# MelansonTech_PSU_IsolatedShuntAmp.net
KiCad netlist of a schematic drawn in Altium Designer
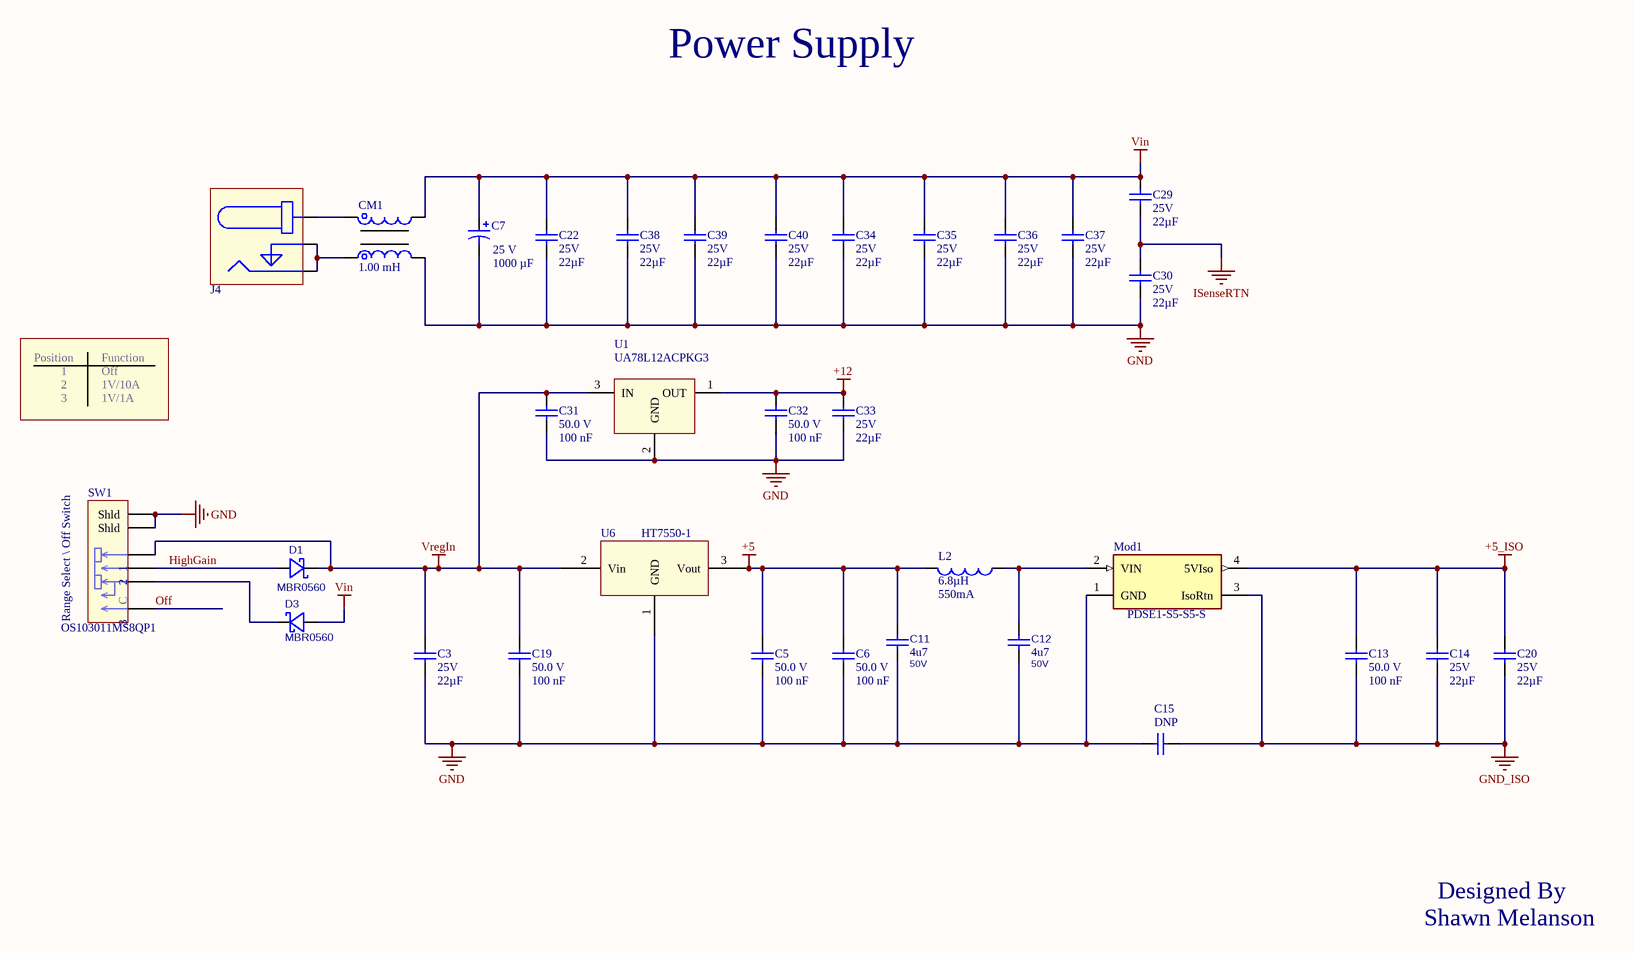
[diagram p0: MelansonTech PSU_IsolatedShuntAmp.SchDoc]

(export (version "E")
  (design (tool "Eeschema 10.0.6"))
  (components
    (comp (ref "C3")
      (value "CL21A226MAQNNNE")
      (footprint "Cap,0805")
      (description "CAP CER 22UF 25V X5R 0805")
      (fields
        (field (name "MANUFACTURER") "Samsung Electro-Mechanics")
        (field (name "TOLERANCE") "±20%")
        (field (name "VOLTAGE - RATED") "25V")
        (field (name "CAPACITANCE") "22µF")
      )
      (libsource (lib "Master Mar2024") (part "Cap,0805,22uF,25V,X5R,±20%,CL21A226MAQNNNE"))
    )
    (comp (ref "C5")
      (value "CC0805KRX7R9BB104")
      (footprint "CAP, 0805, HD")
      (description "CAP CER 0.1UF 50V X7R 0805")
      (fields
        (field (name "VOLTAGE RATING (DC)") "50.0 V")
        (field (name "CAPACITANCE") "100 nF")
        (field (name "MANUFACTURER") "YAGEO")
      )
      (libsource (lib "Master Mar2024") (part "Cap,0805,100nf,50V,5%,CC0805KRX7R9BB104"))
    )
    (comp (ref "C6")
      (value "CC0805KRX7R9BB104")
      (footprint "CAP, 0805, HD")
      (description "CAP CER 0.1UF 50V X7R 0805")
      (fields
        (field (name "VOLTAGE RATING (DC)") "50.0 V")
        (field (name "CAPACITANCE") "100 nF")
        (field (name "MANUFACTURER") "YAGEO")
      )
      (libsource (lib "Master Mar2024") (part "Cap,0805,100nf,50V,5%,CC0805KRX7R9BB104"))
    )
    (comp (ref "C7")
      (value "A750MV108M1EAAE014")
      (footprint "Cap,5mm Lead Spaceing,14mm HIGH,10MM Dia, Polymer - RA1")
      (description "1000 µF 25 V Aluminum - Polymer Capacitors Radial, Can 14mOhm 2000 Hrs @ 105°C")
      (fields
        (field (name "MANUFACTURER") "KEMET")
        (field (name "CAPACITANCE") "1000 µF")
        (field (name "TOLERANCE") "±20%")
        (field (name "VOLTAGE - RATED") "25 V")
      )
      (libsource (lib "Master Mar2024") (part "Cap,Polar,TH,1000uF,25V,Polymer,±20%,A750MV108M1EAAE014"))
    )
    (comp (ref "C11")
      (value "CL31B475KBHNNNE")
      (footprint "Cap, 1206")
      (description "Cap,SMD,MLCC,4u7,50V,X7R,10%,1206")
      (fields
        (field (name "MANUFACTURER") "Samsung")
        (field (name "TOLERANCE") "10%")
        (field (name "CAPACITANCE") "4u7")
        (field (name "VOLTAGE") "50V")
      )
      (libsource (lib "Master JULY2019") (part "Cap,1206,4.7uF,10%,50V,CL31B475KBHNNNE"))
    )
    (comp (ref "C12")
      (value "CL31B475KBHNNNE")
      (footprint "Cap, 1206")
      (description "Cap,SMD,MLCC,4u7,50V,X7R,10%,1206")
      (fields
        (field (name "MANUFACTURER") "Samsung")
        (field (name "TOLERANCE") "10%")
        (field (name "CAPACITANCE") "4u7")
        (field (name "VOLTAGE") "50V")
      )
      (libsource (lib "Master JULY2019") (part "Cap,1206,4.7uF,10%,50V,CL31B475KBHNNNE"))
    )
    (comp (ref "C13")
      (value "CC0805KRX7R9BB104")
      (footprint "Cap,0805")
      (description "CAP CER 0.1UF 50V X7R 0805")
      (fields
        (field (name "VOLTAGE RATING (DC)") "50.0 V")
        (field (name "CAPACITANCE") "100 nF")
        (field (name "MANUFACTURER") "YAGEO")
      )
      (libsource (lib "Master Mar2024") (part "Cap,0805,100nf,50V,5%,CC0805KRX7R9BB104"))
    )
    (comp (ref "C14")
      (value "CL21A226MAQNNNE")
      (footprint "Cap,0805")
      (description "CAP CER 22UF 25V X5R 0805")
      (fields
        (field (name "MANUFACTURER") "Samsung Electro-Mechanics")
        (field (name "TOLERANCE") "±20%")
        (field (name "VOLTAGE - RATED") "25V")
        (field (name "CAPACITANCE") "22µF")
      )
      (libsource (lib "Master Mar2024") (part "Cap,0805,22uF,25V,X5R,±20%,CL21A226MAQNNNE"))
    )
    (comp (ref "C15")
      (value "S102K33Y5PP63K5R")
      (footprint "Cap, 5mm Lead Spaceing, 4mm dai")
      (description "CAP CER 1000PF 2KV Y5P RADIAL")
      (fields (field (name "MANUFACTURER") "Vishay BC Components") (field (name "TOLERANCE") "±10%"))
      (libsource (lib "Master JULY2019") (part "Cap,TH,Ceramic,5mm Spacing,1nF,2kV, S102K33Y5PP63K5R"))
    )
    (comp (ref "C19")
      (value "CC0805KRX7R9BB104")
      (footprint "CAP, 0805, HD")
      (description "CAP CER 0.1UF 50V X7R 0805")
      (fields
        (field (name "VOLTAGE RATING (DC)") "50.0 V")
        (field (name "CAPACITANCE") "100 nF")
        (field (name "MANUFACTURER") "YAGEO")
      )
      (libsource (lib "Master Mar2024") (part "Cap,0805,100nf,50V,5%,CC0805KRX7R9BB104"))
    )
    (comp (ref "C20")
      (value "CL21A226MAQNNNE")
      (footprint "Cap,0805")
      (description "CAP CER 22UF 25V X5R 0805")
      (fields
        (field (name "MANUFACTURER") "Samsung Electro-Mechanics")
        (field (name "TOLERANCE") "±20%")
        (field (name "VOLTAGE - RATED") "25V")
        (field (name "CAPACITANCE") "22µF")
      )
      (libsource (lib "Master Mar2024") (part "Cap,0805,22uF,25V,X5R,±20%,CL21A226MAQNNNE"))
    )
    (comp (ref "C22")
      (value "CL21A226MAQNNNE")
      (footprint "Cap,0805")
      (description "CAP CER 22UF 25V X5R 0805")
      (fields
        (field (name "MANUFACTURER") "Samsung Electro-Mechanics")
        (field (name "TOLERANCE") "±20%")
        (field (name "VOLTAGE - RATED") "25V")
        (field (name "CAPACITANCE") "22µF")
      )
      (libsource (lib "Master Mar2024") (part "Cap,0805,22uF,25V,X5R,±20%,CL21A226MAQNNNE"))
    )
    (comp (ref "C29")
      (value "CL21A226MAQNNNE")
      (footprint "Cap,0805")
      (description "CAP CER 22UF 25V X5R 0805")
      (fields
        (field (name "MANUFACTURER") "Samsung Electro-Mechanics")
        (field (name "TOLERANCE") "±20%")
        (field (name "VOLTAGE - RATED") "25V")
        (field (name "CAPACITANCE") "22µF")
      )
      (libsource (lib "Master Mar2024") (part "Cap,0805,22uF,25V,X5R,±20%,CL21A226MAQNNNE"))
    )
    (comp (ref "C30")
      (value "CL21A226MAQNNNE")
      (footprint "Cap,0805")
      (description "CAP CER 22UF 25V X5R 0805")
      (fields
        (field (name "MANUFACTURER") "Samsung Electro-Mechanics")
        (field (name "TOLERANCE") "±20%")
        (field (name "VOLTAGE - RATED") "25V")
        (field (name "CAPACITANCE") "22µF")
      )
      (libsource (lib "Master Mar2024") (part "Cap,0805,22uF,25V,X5R,±20%,CL21A226MAQNNNE"))
    )
    (comp (ref "C31")
      (value "CC0805KRX7R9BB104")
      (footprint "CAP, 0805, HD")
      (description "CAP CER 0.1UF 50V X7R 0805")
      (fields
        (field (name "VOLTAGE RATING (DC)") "50.0 V")
        (field (name "CAPACITANCE") "100 nF")
        (field (name "MANUFACTURER") "YAGEO")
      )
      (libsource (lib "Master Mar2024") (part "Cap,0805,100nf,50V,5%,CC0805KRX7R9BB104"))
    )
    (comp (ref "C32")
      (value "CC0805KRX7R9BB104")
      (footprint "CAP, 0805, HD")
      (description "CAP CER 0.1UF 50V X7R 0805")
      (fields
        (field (name "VOLTAGE RATING (DC)") "50.0 V")
        (field (name "CAPACITANCE") "100 nF")
        (field (name "MANUFACTURER") "YAGEO")
      )
      (libsource (lib "Master Mar2024") (part "Cap,0805,100nf,50V,5%,CC0805KRX7R9BB104"))
    )
    (comp (ref "C33")
      (value "CL21A226MAQNNNE")
      (footprint "Cap,0805")
      (description "CAP CER 22UF 25V X5R 0805")
      (fields
        (field (name "MANUFACTURER") "Samsung Electro-Mechanics")
        (field (name "TOLERANCE") "±20%")
        (field (name "VOLTAGE - RATED") "25V")
        (field (name "CAPACITANCE") "22µF")
      )
      (libsource (lib "Master Mar2024") (part "Cap,0805,22uF,25V,X5R,±20%,CL21A226MAQNNNE"))
    )
    (comp (ref "C34")
      (value "CL21A226MAQNNNE")
      (footprint "Cap,0805")
      (description "CAP CER 22UF 25V X5R 0805")
      (fields
        (field (name "MANUFACTURER") "Samsung Electro-Mechanics")
        (field (name "TOLERANCE") "±20%")
        (field (name "VOLTAGE - RATED") "25V")
        (field (name "CAPACITANCE") "22µF")
      )
      (libsource (lib "Master Mar2024") (part "Cap,0805,22uF,25V,X5R,±20%,CL21A226MAQNNNE"))
    )
    (comp (ref "C35")
      (value "CL21A226MAQNNNE")
      (footprint "Cap,0805")
      (description "CAP CER 22UF 25V X5R 0805")
      (fields
        (field (name "MANUFACTURER") "Samsung Electro-Mechanics")
        (field (name "TOLERANCE") "±20%")
        (field (name "VOLTAGE - RATED") "25V")
        (field (name "CAPACITANCE") "22µF")
      )
      (libsource (lib "Master Mar2024") (part "Cap,0805,22uF,25V,X5R,±20%,CL21A226MAQNNNE"))
    )
    (comp (ref "C36")
      (value "CL21A226MAQNNNE")
      (footprint "Cap,0805")
      (description "CAP CER 22UF 25V X5R 0805")
      (fields
        (field (name "MANUFACTURER") "Samsung Electro-Mechanics")
        (field (name "TOLERANCE") "±20%")
        (field (name "VOLTAGE - RATED") "25V")
        (field (name "CAPACITANCE") "22µF")
      )
      (libsource (lib "Master Mar2024") (part "Cap,0805,22uF,25V,X5R,±20%,CL21A226MAQNNNE"))
    )
    (comp (ref "C37")
      (value "CL21A226MAQNNNE")
      (footprint "Cap,0805")
      (description "CAP CER 22UF 25V X5R 0805")
      (fields
        (field (name "MANUFACTURER") "Samsung Electro-Mechanics")
        (field (name "TOLERANCE") "±20%")
        (field (name "VOLTAGE - RATED") "25V")
        (field (name "CAPACITANCE") "22µF")
      )
      (libsource (lib "Master Mar2024") (part "Cap,0805,22uF,25V,X5R,±20%,CL21A226MAQNNNE"))
    )
    (comp (ref "C38")
      (value "CL21A226MAQNNNE")
      (footprint "Cap,0805")
      (description "CAP CER 22UF 25V X5R 0805")
      (fields
        (field (name "MANUFACTURER") "Samsung Electro-Mechanics")
        (field (name "TOLERANCE") "±20%")
        (field (name "VOLTAGE - RATED") "25V")
        (field (name "CAPACITANCE") "22µF")
      )
      (libsource (lib "Master Mar2024") (part "Cap,0805,22uF,25V,X5R,±20%,CL21A226MAQNNNE"))
    )
    (comp (ref "C39")
      (value "CL21A226MAQNNNE")
      (footprint "Cap,0805")
      (description "CAP CER 22UF 25V X5R 0805")
      (fields
        (field (name "MANUFACTURER") "Samsung Electro-Mechanics")
        (field (name "TOLERANCE") "±20%")
        (field (name "VOLTAGE - RATED") "25V")
        (field (name "CAPACITANCE") "22µF")
      )
      (libsource (lib "Master Mar2024") (part "Cap,0805,22uF,25V,X5R,±20%,CL21A226MAQNNNE"))
    )
    (comp (ref "C40")
      (value "CL21A226MAQNNNE")
      (footprint "Cap,0805")
      (description "CAP CER 22UF 25V X5R 0805")
      (fields
        (field (name "MANUFACTURER") "Samsung Electro-Mechanics")
        (field (name "TOLERANCE") "±20%")
        (field (name "VOLTAGE - RATED") "25V")
        (field (name "CAPACITANCE") "22µF")
      )
      (libsource (lib "Master Mar2024") (part "Cap,0805,22uF,25V,X5R,±20%,CL21A226MAQNNNE"))
    )
    (comp (ref "CM1")
      (value "DR331-105BE")
      (footprint "CM Choke,SMD, DR331")
      (description "CMC 1MH 500MA 2LN SMD")
      (fields (field (name "INDUCTANCE") "1.00 mH"))
      (libsource (lib "Master Mar2024") (part "common mode, 1mH@100kHz, 500mA, SMD,2ln, DR331-105BE"))
    )
    (comp (ref "D1")
      (value "MBR0560")
      (footprint "SOD123")
      (description "Dio,Sig,Schtky,0.5A,60V,SOD123")
      (fields (field (name "MANUFACTURER") "MCC") (field (name "VOLTAGE") "60V"))
      (libsource (lib "Master DEC 2020") (part "Diode,SOD123,Shottky,60V,0.5A,MBR0560"))
    )
    (comp (ref "D3")
      (value "MBR0560")
      (footprint "SOD123")
      (description "Dio,Sig,Schtky,0.5A,60V,SOD123")
      (fields (field (name "MANUFACTURER") "MCC") (field (name "VOLTAGE") "60V"))
      (libsource (lib "Master DEC 2020") (part "Diode,SOD123,Shottky,60V,0.5A,MBR0560"))
    )
    (comp (ref "J4")
      (value "PJ-002A")
      (footprint "Connector,Barrel,2.1mm,5.5mm,DC power Jack")
      (description "Power Barrel Connector Jack 2.10mm ID (0.083\"), 5.50mm OD (0.217\") Through Hole, Right Angle")
      (fields (field (name "MANUFACTURER") "CUI Inc."))
      (libsource (lib "Master Nov2021") (part "Connector,Barrel,ID 2.1mm,OD 5.5mm,Power Connect, PJ-002A"))
    )
    (comp (ref "L2")
      (value "MLZ2012N6R8LT000")
      (footprint "Ind, 0805")
      (description "FIXED IND 6.8UH 550MA 250 MOHM")
      (fields
        (field (name "MANUFACTURER") "TDK Corporation")
        (field (name "TOLERANCE") "±20%")
        (field (name "INDUCTANCE") "6.8µH")
        (field (name "CURRENT RATING (AMPS)") "550mA")
      )
      (libsource (lib "Master JULY2019") (part "Ind,0805,6.8uH,550mA,0.25Ω, MLZ2012N6R8LT000"))
    )
    (comp (ref "Mod1")
      (value "PDSE1-S5-S5-S")
      (footprint "CONV_PDSE1-S5-S5-S")
      (description "DC-DC ISOLATED, 1 W, 4.5-5.5 VDC")
      (fields (field (name "MANUFACTURER") "CUI Inc."))
      (libsource (lib "Master JULY2019") (part "Mod,PSU,4.5-5.5Vin,5Vout,1W, PDSE1-S5-S5-S"))
    )
    (comp (ref "SW1")
      (value "OS103011MS8QP1")
      (footprint "Switch,Slide,.SP3T, OS103011 -Side")
      (description "SWITCH SLIDE SP3T 100MA 12V")
      (fields (field (name "MANUFACTURER") "C&K"))
      (libsource (lib "Master Nov2021") (part "Switch,TH,Slide,SP3T,100MA,12V,OS103011MS8QP1"))
    )
    (comp (ref "U1")
      (value "UA78L12ACPKG3")
      (footprint "SOT89-3")
      (description "IC REG LINEAR 12V 100MA SOT89-3")
      (fields (field (name "MANUFACTURER") "Texas Instruments"))
      (libsource (lib "Master Nov2021") (part "Reg,Linear,Pos,Fixed,12Vout,27Vin,100mA,UA78L12ACPKG3"))
    )
    (comp (ref "U6")
      (value "HT7550-1")
      (footprint "SOT89-3")
      (description "LOW DROPOUT REGULATORS(LDO) POSITIVE FIXED 55MV @ 1MA 30V 5V 150MA SOT-89(SOT-89-3) ROHS")
      (fields
        (field (name "LCSC PART #") "C16106")
        (field (name "MANUFACTURER") "Holtek Semicon")
        (field (name "MFG P/N") "HT7550-1")
      )
      (libsource (lib "Master DEC 2020") (part "Reg,Linear,Fixed,SOT-89-3,30Vin,5Vout,150mA,HT7550-1"))
    )
  )
  (nets
    (net (code "1") (name "+5") (class "Default")
      (node (ref "C11") (pin "2") (pintype "passive"))
      (node (ref "C5") (pin "2") (pinfunction "2_2") (pintype "passive"))
      (node (ref "C6") (pin "2") (pinfunction "2_2") (pintype "passive"))
      (node (ref "L2") (pin "2") (pinfunction "2_2") (pintype "passive"))
      (node (ref "U6") (pin "3") (pinfunction "Vout_3") (pintype "passive"))
    )
    (net (code "2") (name "+5_ISO") (class "Default")
      (node (ref "C13") (pin "2") (pinfunction "2_2") (pintype "passive"))
      (node (ref "C14") (pin "2") (pinfunction "2_2") (pintype "passive"))
      (node (ref "C20") (pin "2") (pinfunction "2_2") (pintype "passive"))
      (node (ref "Mod1") (pin "4") (pinfunction "5VIso_4") (pintype "output"))
    )
    (net (code "3") (name "+12") (class "Default")
      (node (ref "C32") (pin "2") (pinfunction "2_2") (pintype "passive"))
      (node (ref "C33") (pin "2") (pinfunction "2_2") (pintype "passive"))
      (node (ref "U1") (pin "1") (pinfunction "OUT_1") (pintype "passive"))
    )
    (net (code "4") (name "/HighGain") (class "Default")
      (node (ref "D1") (pin "2") (pinfunction "A_2") (pintype "passive"))
      (node (ref "SW1") (pin "3") (pinfunction "3_3") (pintype "passive"))
    )
    (net (code "5") (name "/Off") (class "Default")
      (node (ref "SW1") (pin "1") (pinfunction "1_1") (pintype "passive"))
    )
    (net (code "6") (name "GND") (class "Default")
      (node (ref "C11") (pin "1") (pintype "passive"))
      (node (ref "C12") (pin "1") (pintype "passive"))
      (node (ref "C15") (pin "2") (pinfunction "2_2") (pintype "passive"))
      (node (ref "C19") (pin "1") (pinfunction "1_1") (pintype "passive"))
      (node (ref "C22") (pin "1") (pinfunction "1_1") (pintype "passive"))
      (node (ref "C3") (pin "1") (pinfunction "1_1") (pintype "passive"))
      (node (ref "C30") (pin "1") (pinfunction "1_1") (pintype "passive"))
      (node (ref "C31") (pin "1") (pinfunction "1_1") (pintype "passive"))
      (node (ref "C32") (pin "1") (pinfunction "1_1") (pintype "passive"))
      (node (ref "C33") (pin "1") (pinfunction "1_1") (pintype "passive"))
      (node (ref "C34") (pin "1") (pinfunction "1_1") (pintype "passive"))
      (node (ref "C35") (pin "1") (pinfunction "1_1") (pintype "passive"))
      (node (ref "C36") (pin "1") (pinfunction "1_1") (pintype "passive"))
      (node (ref "C37") (pin "1") (pinfunction "1_1") (pintype "passive"))
      (node (ref "C38") (pin "1") (pinfunction "1_1") (pintype "passive"))
      (node (ref "C39") (pin "1") (pinfunction "1_1") (pintype "passive"))
      (node (ref "C40") (pin "1") (pinfunction "1_1") (pintype "passive"))
      (node (ref "C5") (pin "1") (pinfunction "1_1") (pintype "passive"))
      (node (ref "C6") (pin "1") (pinfunction "1_1") (pintype "passive"))
      (node (ref "C7") (pin "2") (pinfunction "2_2") (pintype "passive"))
      (node (ref "CM1") (pin "4") (pinfunction "4_4") (pintype "passive"))
      (node (ref "Mod1") (pin "1") (pinfunction "GND_1") (pintype "power_in"))
      (node (ref "SW1") (pin "5") (pinfunction "Shld_5") (pintype "passive"))
      (node (ref "SW1") (pin "6") (pinfunction "Shld_6") (pintype "passive"))
      (node (ref "U1") (pin "2") (pinfunction "GND_2") (pintype "passive"))
      (node (ref "U6") (pin "1") (pinfunction "GND_1") (pintype "passive"))
    )
    (net (code "7") (name "GND_ISO") (class "Default")
      (node (ref "C13") (pin "1") (pinfunction "1_1") (pintype "passive"))
      (node (ref "C14") (pin "1") (pinfunction "1_1") (pintype "passive"))
      (node (ref "C15") (pin "1") (pinfunction "1_1") (pintype "passive"))
      (node (ref "C20") (pin "1") (pinfunction "1_1") (pintype "passive"))
      (node (ref "Mod1") (pin "3") (pinfunction "IsoRtn_3") (pintype "power_in"))
    )
    (net (code "8") (name "ISenseRTN") (class "Default")
      (node (ref "C29") (pin "1") (pinfunction "1_1") (pintype "passive"))
      (node (ref "C30") (pin "2") (pinfunction "2_2") (pintype "passive"))
    )
    (net (code "9") (name "Net-(CM1-Pad1)") (class "Default")
      (node (ref "CM1") (pin "1") (pinfunction "1_1") (pintype "passive"))
      (node (ref "J4") (pin "1") (pinfunction "1_1") (pintype "passive"))
    )
    (net (code "10") (name "Net-(CM1-Pad3)") (class "Default")
      (node (ref "CM1") (pin "3") (pinfunction "3_3") (pintype "passive"))
      (node (ref "J4") (pin "2") (pinfunction "2_2") (pintype "passive"))
      (node (ref "J4") (pin "3") (pinfunction "3_3") (pintype "passive"))
    )
    (net (code "11") (name "Net-(D3-C)") (class "Default")
      (node (ref "D3") (pin "1") (pinfunction "C_1") (pintype "passive"))
      (node (ref "SW1") (pin "2") (pinfunction "2_2") (pintype "passive"))
    )
    (net (code "12") (name "Net-(Mod1-VIN)") (class "Default")
      (node (ref "C12") (pin "2") (pintype "passive"))
      (node (ref "L2") (pin "1") (pinfunction "1_1") (pintype "passive"))
      (node (ref "Mod1") (pin "2") (pinfunction "VIN_2") (pintype "input"))
    )
    (net (code "13") (name "Vin") (class "Default")
      (node (ref "C22") (pin "2") (pinfunction "2_2") (pintype "passive"))
      (node (ref "C29") (pin "2") (pinfunction "2_2") (pintype "passive"))
      (node (ref "C34") (pin "2") (pinfunction "2_2") (pintype "passive"))
      (node (ref "C35") (pin "2") (pinfunction "2_2") (pintype "passive"))
      (node (ref "C36") (pin "2") (pinfunction "2_2") (pintype "passive"))
      (node (ref "C37") (pin "2") (pinfunction "2_2") (pintype "passive"))
      (node (ref "C38") (pin "2") (pinfunction "2_2") (pintype "passive"))
      (node (ref "C39") (pin "2") (pinfunction "2_2") (pintype "passive"))
      (node (ref "C40") (pin "2") (pinfunction "2_2") (pintype "passive"))
      (node (ref "C7") (pin "1") (pinfunction "1_1") (pintype "passive"))
      (node (ref "CM1") (pin "2") (pinfunction "2_2") (pintype "passive"))
      (node (ref "D3") (pin "2") (pinfunction "A_2") (pintype "passive"))
    )
    (net (code "14") (name "VregIn") (class "Default")
      (node (ref "C19") (pin "2") (pinfunction "2_2") (pintype "passive"))
      (node (ref "C3") (pin "2") (pinfunction "2_2") (pintype "passive"))
      (node (ref "C31") (pin "2") (pinfunction "2_2") (pintype "passive"))
      (node (ref "D1") (pin "1") (pinfunction "C_1") (pintype "passive"))
      (node (ref "SW1") (pin "4") (pinfunction "4_4") (pintype "passive"))
      (node (ref "U1") (pin "3") (pinfunction "IN_3") (pintype "passive"))
      (node (ref "U6") (pin "2") (pinfunction "Vin_2") (pintype "passive"))
    )
  )
)
